# Adafruit_NeoKey_Trinkey.net
KiCad netlist of a schematic drawn in EAGLE
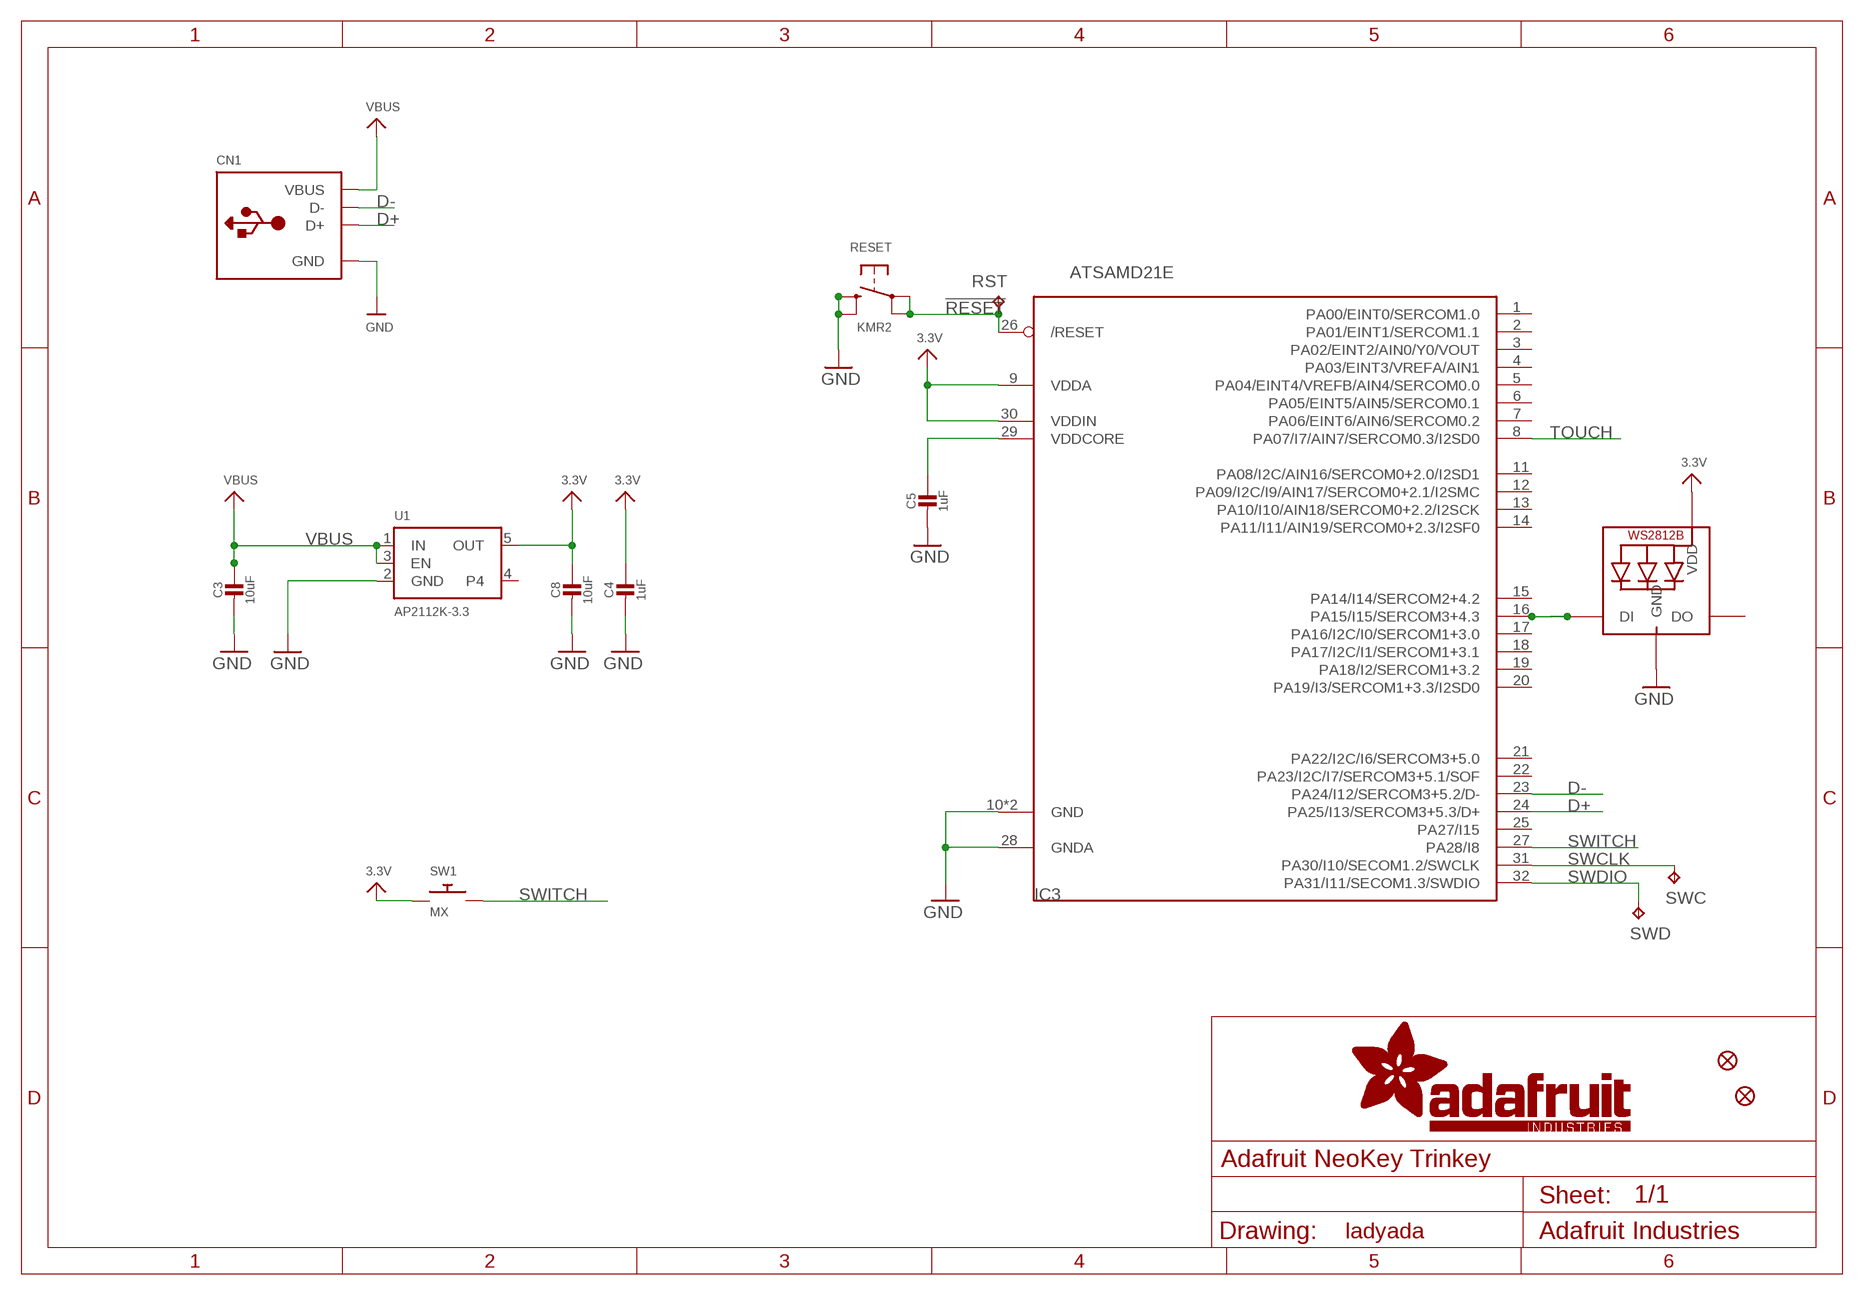
[diagram p0: schematic, sheet 1]

(export (version "E")
  (design (tool "Eeschema 10.0.6"))
  (components
    (comp (ref "C3")
      (value "10uF")
      (footprint "eagle-import:0805-NO")
      (libsource (lib "eagle-import") (part "CAP_CERAMIC0805-NOOUTLINE"))
    )
    (comp (ref "C4")
      (value "1uF")
      (footprint "eagle-import:0603-NO")
      (libsource (lib "eagle-import") (part "CAP_CERAMIC0603_NO"))
    )
    (comp (ref "C5")
      (value "1uF")
      (footprint "eagle-import:0603-NO")
      (libsource (lib "eagle-import") (part "CAP_CERAMIC0603_NO"))
    )
    (comp (ref "C8")
      (value "10uF")
      (footprint "eagle-import:0805-NO")
      (libsource (lib "eagle-import") (part "CAP_CERAMIC0805-NOOUTLINE"))
    )
    (comp (ref "CN1")
      (value "USB_TYPEAPCB")
      (footprint "eagle-import:USBA_PCB")
      (libsource (lib "eagle-import") (part "USB_TYPEAPCB"))
    )
    (comp (ref "FID1")
      (value "FIDUCIAL_1MM")
      (footprint "eagle-import:FIDUCIAL_1MM")
      (libsource (lib "eagle-import") (part "FIDUCIAL_1MM"))
    )
    (comp (ref "FID2")
      (value "FIDUCIAL_1MM")
      (footprint "eagle-import:FIDUCIAL_1MM")
      (libsource (lib "eagle-import") (part "FIDUCIAL_1MM"))
    )
    (comp (ref "IC3")
      (value "ATSAMD21E")
      (footprint "eagle-import:QFN32_5MM")
      (libsource (lib "eagle-import") (part "ATSAMD21E"))
    )
    (comp (ref "LED1")
      (value "WS2812B_SK6812E")
      (footprint "eagle-import:NEO3535_REVERSE")
      (libsource (lib "eagle-import") (part "WS2812B_SK6812E"))
    )
    (comp (ref "RESET")
      (value "KMR2")
      (footprint "eagle-import:BTN_KMR2_4.6X2.8")
      (libsource (lib "eagle-import") (part "SWITCH_TACT_SMT4.6X2.8"))
    )
    (comp (ref "RST")
      (value "RST")
      (footprint "eagle-import:TP16R")
      (libsource (lib "eagle-import") (part "TPTP16R"))
    )
    (comp (ref "SW1")
      (value "MX")
      (footprint "eagle-import:KAILH_BOX_MX_NOSTABILIZERS")
      (libsource (lib "eagle-import") (part "SWITCH_PUSHBUTTON_KAILH_THMSIMPLE"))
    )
    (comp (ref "SWC")
      (value "SWC")
      (footprint "eagle-import:TP15R")
      (libsource (lib "eagle-import") (part "TPTP15R"))
    )
    (comp (ref "SWD")
      (value "SWD")
      (footprint "eagle-import:TP15R")
      (libsource (lib "eagle-import") (part "TPTP15R"))
    )
    (comp (ref "U1")
      (value "AP2112K-3.3")
      (footprint "eagle-import:SOT23-5")
      (libsource (lib "eagle-import") (part "VREG_SOT23-5"))
    )
  )
  (nets
    (net (code "1") (name "/D+") (class "Default")
      (node (ref "CN1") (pin "USB_PLUS") (pinfunction "D+_USB_PLUS") (pintype "bidirectional"))
      (node (ref "IC3") (pin "24") (pinfunction "PA25/I13/SERCOM3+5.3/D+_24") (pintype "bidirectional"))
    )
    (net (code "2") (name "/D-") (class "Default")
      (node (ref "CN1") (pin "USB_NEG") (pinfunction "D-_USB_NEG") (pintype "bidirectional"))
      (node (ref "IC3") (pin "23") (pinfunction "PA24/I12/SERCOM3+5.2/D-_23") (pintype "bidirectional"))
    )
    (net (code "3") (name "/SWCLK") (class "Default")
      (node (ref "IC3") (pin "31") (pinfunction "PA30/I10/SECOM1.2/SWCLK_31") (pintype "bidirectional"))
      (node (ref "SWC") (pin "TP") (pinfunction "TP_TP") (pintype "input"))
    )
    (net (code "4") (name "/SWDIO") (class "Default")
      (node (ref "IC3") (pin "32") (pinfunction "PA31/I11/SECOM1.3/SWDIO_32") (pintype "bidirectional"))
      (node (ref "SWD") (pin "TP") (pinfunction "TP_TP") (pintype "input"))
    )
    (net (code "5") (name "/SWITCH") (class "Default")
      (node (ref "IC3") (pin "27") (pinfunction "PA28/I8_27") (pintype "bidirectional"))
      (node (ref "SW1") (pin "2") (pinfunction "P$2_2") (pintype "passive"))
    )
    (net (code "6") (name "/TOUCH") (class "Default")
      (node (ref "IC3") (pin "8") (pinfunction "PA07/I7/AIN7/SERCOM0.3/I2SD0_8") (pintype "bidirectional"))
    )
    (net (code "7") (name "/~{RESET}") (class "Default")
      (node (ref "IC3") (pin "26") (pinfunction "/RESET_26") (pintype "bidirectional"))
      (node (ref "RESET") (pin "A") (pinfunction "P_A") (pintype "passive"))
      (node (ref "RESET") (pin "A'") (pinfunction "P1_A'") (pintype "passive"))
      (node (ref "RST") (pin "TP") (pinfunction "TP_TP") (pintype "input"))
    )
    (net (code "8") (name "3.3V") (class "Default")
      (node (ref "C4") (pin "1") (pinfunction "1_1") (pintype "passive"))
      (node (ref "C8") (pin "1") (pinfunction "1_1") (pintype "passive"))
      (node (ref "IC3") (pin "30") (pinfunction "VDDIN_30") (pintype "power_in"))
      (node (ref "IC3") (pin "9") (pinfunction "VDDA_9") (pintype "power_in"))
      (node (ref "LED1") (pin "1-VDD") (pinfunction "VDD_1-VDD") (pintype "power_in"))
      (node (ref "SW1") (pin "1") (pinfunction "P$1_1") (pintype "passive"))
      (node (ref "U1") (pin "5") (pinfunction "OUT_5") (pintype "power_in"))
    )
    (net (code "9") (name "GND") (class "Default")
      (node (ref "C3") (pin "2") (pinfunction "2_2") (pintype "passive"))
      (node (ref "C4") (pin "2") (pinfunction "2_2") (pintype "passive"))
      (node (ref "C5") (pin "2") (pinfunction "2_2") (pintype "passive"))
      (node (ref "C8") (pin "2") (pinfunction "2_2") (pintype "passive"))
      (node (ref "CN1") (pin "GND") (pinfunction "GND_GND") (pintype "power_in"))
      (node (ref "IC3") (pin "10") (pinfunction "GND_10") (pintype "power_in"))
      (node (ref "IC3") (pin "28") (pinfunction "GNDA_28") (pintype "power_in"))
      (node (ref "IC3") (pin "33") (pinfunction "GND_33") (pintype "power_in"))
      (node (ref "LED1") (pin "3-GND") (pinfunction "GND_3-GND") (pintype "power_in"))
      (node (ref "RESET") (pin "B") (pinfunction "S_B") (pintype "passive"))
      (node (ref "RESET") (pin "B'") (pinfunction "S1_B'") (pintype "passive"))
      (node (ref "U1") (pin "2") (pinfunction "GND_2") (pintype "power_in"))
    )
    (net (code "10") (name "Net-(IC3-PA15{slash}I15{slash}SERCOM3+4.3)") (class "Default")
      (node (ref "IC3") (pin "16") (pinfunction "PA15/I15/SERCOM3+4.3_16") (pintype "bidirectional"))
      (node (ref "LED1") (pin "4-DIN") (pinfunction "DI_4-DIN") (pintype "input"))
    )
    (net (code "11") (name "Net-(IC3-VDDCORE)") (class "Default")
      (node (ref "C5") (pin "1") (pinfunction "1_1") (pintype "passive"))
      (node (ref "IC3") (pin "29") (pinfunction "VDDCORE_29") (pintype "power_in"))
    )
    (net (code "12") (name "VBUS") (class "Default")
      (node (ref "C3") (pin "1") (pinfunction "1_1") (pintype "passive"))
      (node (ref "CN1") (pin "VCC") (pinfunction "VBUS_VCC") (pintype "power_in"))
      (node (ref "U1") (pin "1") (pinfunction "IN_1") (pintype "power_in"))
      (node (ref "U1") (pin "3") (pinfunction "EN_3") (pintype "input"))
    )
    (net (code "13") (name "unconnected-(IC3-PA00{slash}EINT0{slash}SERCOM1.0-Pad1)") (class "Default")
      (node (ref "IC3") (pin "1") (pinfunction "PA00/EINT0/SERCOM1.0_1") (pintype "bidirectional"))
    )
    (net (code "14") (name "unconnected-(IC3-PA01{slash}EINT1{slash}SERCOM1.1-Pad2)") (class "Default")
      (node (ref "IC3") (pin "2") (pinfunction "PA01/EINT1/SERCOM1.1_2") (pintype "bidirectional"))
    )
    (net (code "15") (name "unconnected-(IC3-PA02{slash}EINT2{slash}AIN0{slash}Y0{slash}VOUT-Pad3)") (class "Default")
      (node (ref "IC3") (pin "3") (pinfunction "PA02/EINT2/AIN0/Y0/VOUT_3") (pintype "bidirectional"))
    )
    (net (code "16") (name "unconnected-(IC3-PA03{slash}EINT3{slash}VREFA{slash}AIN1-Pad4)") (class "Default")
      (node (ref "IC3") (pin "4") (pinfunction "PA03/EINT3/VREFA/AIN1_4") (pintype "bidirectional"))
    )
    (net (code "17") (name "unconnected-(IC3-PA04{slash}EINT4{slash}VREFB{slash}AIN4{slash}SERCOM0.0-Pad5)") (class "Default")
      (node (ref "IC3") (pin "5") (pinfunction "PA04/EINT4/VREFB/AIN4/SERCOM0.0_5") (pintype "bidirectional"))
    )
    (net (code "18") (name "unconnected-(IC3-PA05{slash}EINT5{slash}AIN5{slash}SERCOM0.1-Pad6)") (class "Default")
      (node (ref "IC3") (pin "6") (pinfunction "PA05/EINT5/AIN5/SERCOM0.1_6") (pintype "bidirectional"))
    )
    (net (code "19") (name "unconnected-(IC3-PA06{slash}EINT6{slash}AIN6{slash}SERCOM0.2-Pad7)") (class "Default")
      (node (ref "IC3") (pin "7") (pinfunction "PA06/EINT6/AIN6/SERCOM0.2_7") (pintype "bidirectional"))
    )
    (net (code "20") (name "unconnected-(IC3-PA08{slash}I2C{slash}AIN16{slash}SERCOM0+2.0{slash}I2SD1-Pad11)") (class "Default")
      (node (ref "IC3") (pin "11") (pinfunction "PA08/I2C/AIN16/SERCOM0+2.0/I2SD1_11") (pintype "bidirectional"))
    )
    (net (code "21") (name "unconnected-(IC3-PA09{slash}I2C{slash}I9{slash}AIN17{slash}SERCOM0+2.1{slash}I2SMC-Pad12)") (class "Default")
      (node (ref "IC3") (pin "12") (pinfunction "PA09/I2C/I9/AIN17/SERCOM0+2.1/I2SMC_12") (pintype "bidirectional"))
    )
    (net (code "22") (name "unconnected-(IC3-PA10{slash}I10{slash}AIN18{slash}SERCOM0+2.2{slash}I2SCK-Pad13)") (class "Default")
      (node (ref "IC3") (pin "13") (pinfunction "PA10/I10/AIN18/SERCOM0+2.2/I2SCK_13") (pintype "bidirectional"))
    )
    (net (code "23") (name "unconnected-(IC3-PA11{slash}I11{slash}AIN19{slash}SERCOM0+2.3{slash}I2SF0-Pad14)") (class "Default")
      (node (ref "IC3") (pin "14") (pinfunction "PA11/I11/AIN19/SERCOM0+2.3/I2SF0_14") (pintype "bidirectional"))
    )
    (net (code "24") (name "unconnected-(IC3-PA14{slash}I14{slash}SERCOM2+4.2-Pad15)") (class "Default")
      (node (ref "IC3") (pin "15") (pinfunction "PA14/I14/SERCOM2+4.2_15") (pintype "bidirectional"))
    )
    (net (code "25") (name "unconnected-(IC3-PA16{slash}I2C{slash}I0{slash}SERCOM1+3.0-Pad17)") (class "Default")
      (node (ref "IC3") (pin "17") (pinfunction "PA16/I2C/I0/SERCOM1+3.0_17") (pintype "bidirectional"))
    )
    (net (code "26") (name "unconnected-(IC3-PA17{slash}I2C{slash}I1{slash}SERCOM1+3.1-Pad18)") (class "Default")
      (node (ref "IC3") (pin "18") (pinfunction "PA17/I2C/I1/SERCOM1+3.1_18") (pintype "bidirectional"))
    )
    (net (code "27") (name "unconnected-(IC3-PA18{slash}I2{slash}SERCOM1+3.2-Pad19)") (class "Default")
      (node (ref "IC3") (pin "19") (pinfunction "PA18/I2/SERCOM1+3.2_19") (pintype "bidirectional"))
    )
    (net (code "28") (name "unconnected-(IC3-PA19{slash}I3{slash}SERCOM1+3.3{slash}I2SD0-Pad20)") (class "Default")
      (node (ref "IC3") (pin "20") (pinfunction "PA19/I3/SERCOM1+3.3/I2SD0_20") (pintype "bidirectional"))
    )
    (net (code "29") (name "unconnected-(IC3-PA22{slash}I2C{slash}I6{slash}SERCOM3+5.0-Pad21)") (class "Default")
      (node (ref "IC3") (pin "21") (pinfunction "PA22/I2C/I6/SERCOM3+5.0_21") (pintype "bidirectional"))
    )
    (net (code "30") (name "unconnected-(IC3-PA23{slash}I2C{slash}I7{slash}SERCOM3+5.1{slash}SOF-Pad22)") (class "Default")
      (node (ref "IC3") (pin "22") (pinfunction "PA23/I2C/I7/SERCOM3+5.1/SOF_22") (pintype "bidirectional"))
    )
    (net (code "31") (name "unconnected-(IC3-PA27{slash}I15-Pad25)") (class "Default")
      (node (ref "IC3") (pin "25") (pinfunction "PA27/I15_25") (pintype "bidirectional"))
    )
    (net (code "32") (name "unconnected-(LED1-DO-Pad2-DOUT)") (class "Default")
      (node (ref "LED1") (pin "2-DOUT") (pinfunction "DO_2-DOUT") (pintype "output"))
    )
    (net (code "33") (name "unconnected-(U1-P4-Pad4)") (class "Default")
      (node (ref "U1") (pin "4") (pinfunction "P4_4") (pintype "bidirectional"))
    )
  )
)
